# Carranco_shield.net
KiCad netlist of a schematic drawn in EAGLE
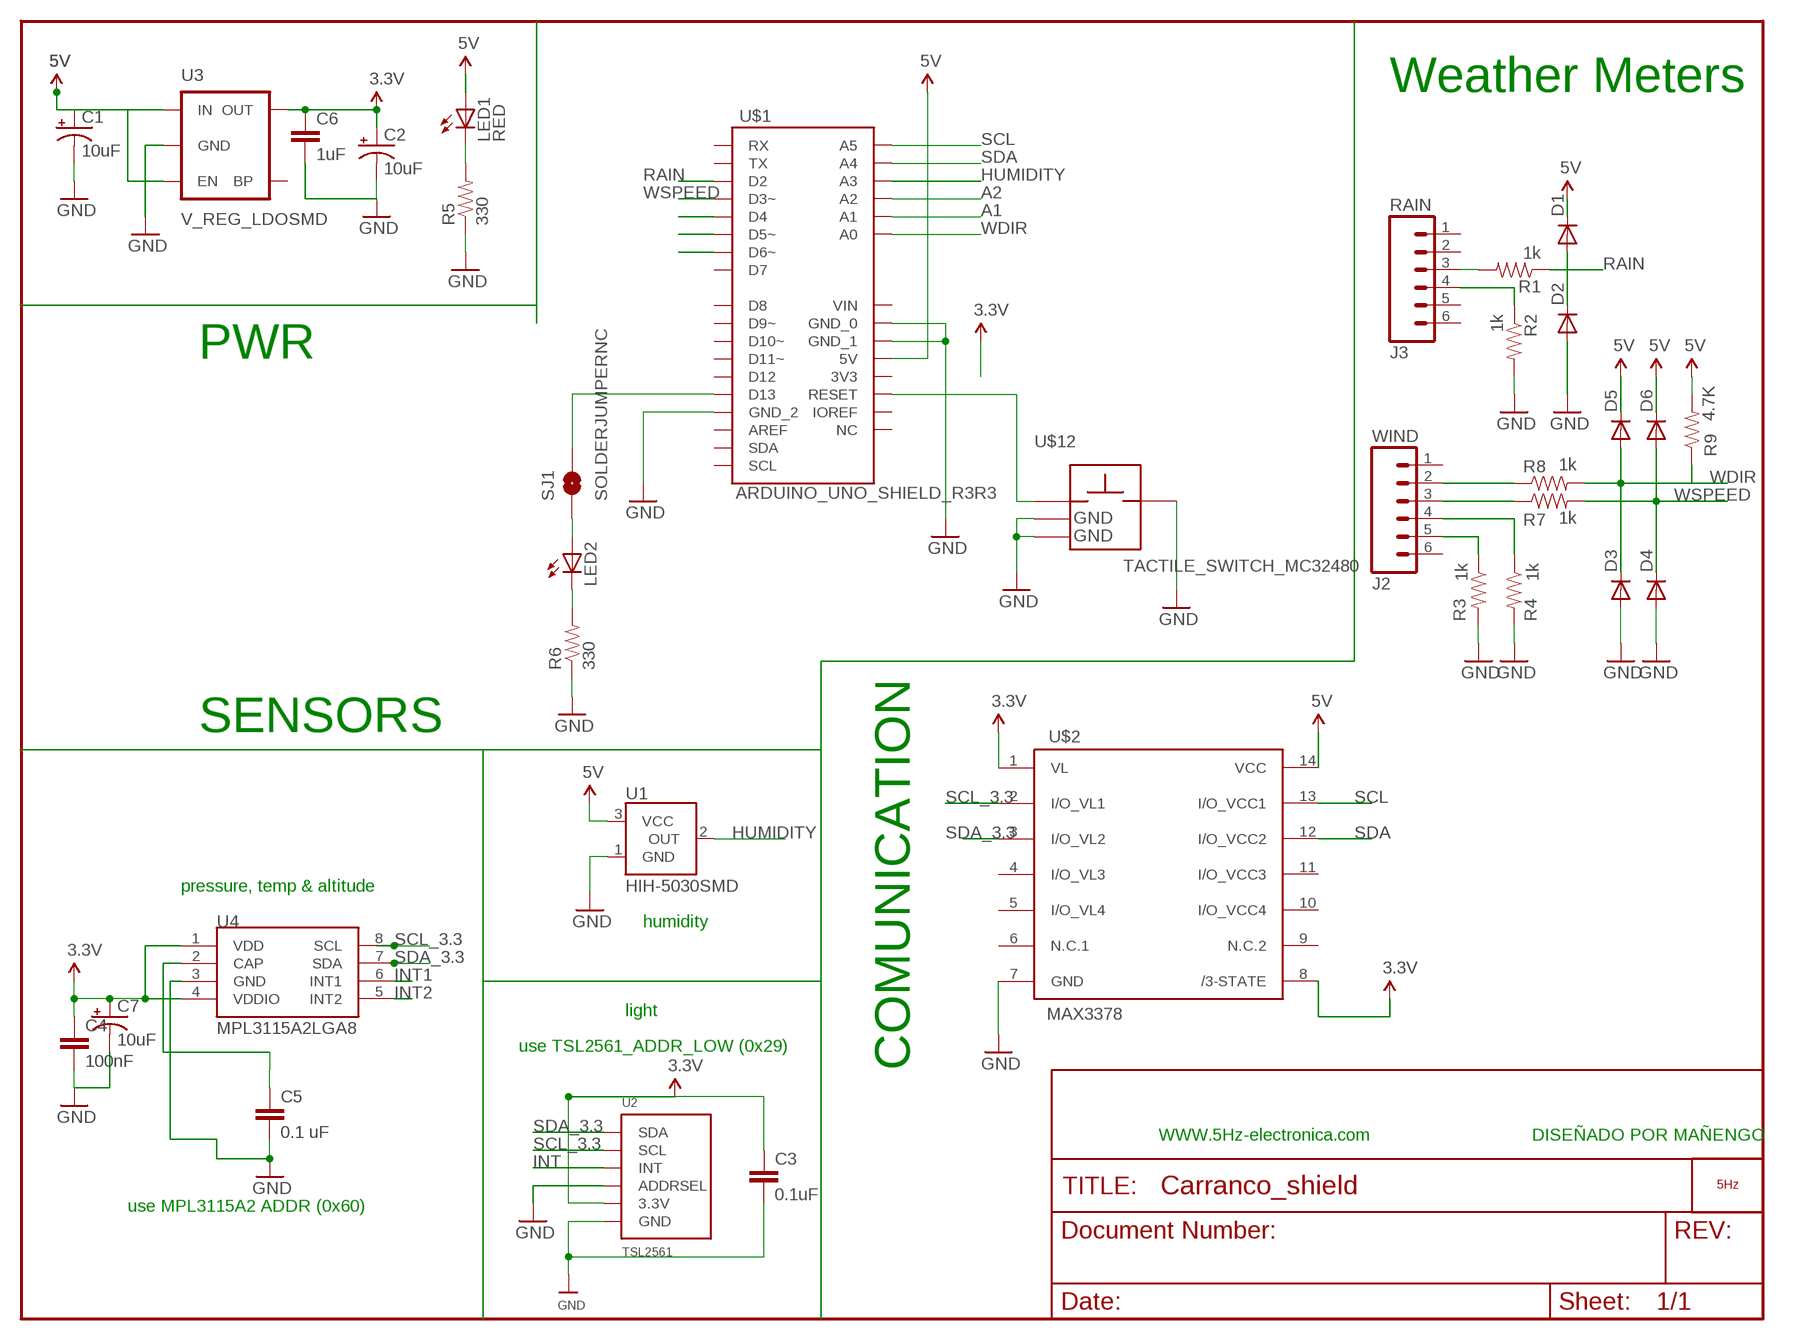
[diagram p0: schematic, sheet 1]

(export (version "E")
  (design (tool "Eeschema 10.0.6"))
  (components
    (comp (ref "C1")
      (value "10uF")
      (footprint "eagle-import:EIA3216")
      (libsource (lib "eagle-import") (part "CAP_POL1206"))
    )
    (comp (ref "C2")
      (value "10uF")
      (footprint "eagle-import:EIA3216")
      (libsource (lib "eagle-import") (part "CAP_POL1206"))
    )
    (comp (ref "C3")
      (value "0.1uF")
      (footprint "eagle-import:0603-CAP")
      (libsource (lib "eagle-import") (part "CAP0603-CAP"))
    )
    (comp (ref "C4")
      (value "100nF")
      (footprint "eagle-import:0603-CAP")
      (libsource (lib "eagle-import") (part "CAP0603-CAP"))
    )
    (comp (ref "C5")
      (value "0.1 uF")
      (footprint "eagle-import:0603-CAP")
      (libsource (lib "eagle-import") (part "CAP0603-CAP"))
    )
    (comp (ref "C6")
      (value "1uF")
      (footprint "eagle-import:0603-CAP")
      (libsource (lib "eagle-import") (part "CAP0603-CAP"))
    )
    (comp (ref "C7")
      (value "10uF")
      (footprint "eagle-import:EIA3216")
      (libsource (lib "eagle-import") (part "CAP_POL1206"))
    )
    (comp (ref "D1")
      (value "DIODESOD")
      (footprint "eagle-import:SOD-323")
      (libsource (lib "eagle-import") (part "DIODESOD"))
    )
    (comp (ref "D2")
      (value "DIODESOD")
      (footprint "eagle-import:SOD-323")
      (libsource (lib "eagle-import") (part "DIODESOD"))
    )
    (comp (ref "D3")
      (value "DIODESOD")
      (footprint "eagle-import:SOD-323")
      (libsource (lib "eagle-import") (part "DIODESOD"))
    )
    (comp (ref "D4")
      (value "DIODESOD")
      (footprint "eagle-import:SOD-323")
      (libsource (lib "eagle-import") (part "DIODESOD"))
    )
    (comp (ref "D5")
      (value "DIODESOD")
      (footprint "eagle-import:SOD-323")
      (libsource (lib "eagle-import") (part "DIODESOD"))
    )
    (comp (ref "D6")
      (value "DIODESOD")
      (footprint "eagle-import:SOD-323")
      (libsource (lib "eagle-import") (part "DIODESOD"))
    )
    (comp (ref "J2")
      (value "WIND")
      (footprint "eagle-import:RJ11-6")
      (libsource (lib "eagle-import") (part "RJ11-6PTH"))
    )
    (comp (ref "J3")
      (value "RAIN")
      (footprint "eagle-import:RJ11-6")
      (libsource (lib "eagle-import") (part "RJ11-6PTH"))
    )
    (comp (ref "LED1")
      (value "RED")
      (footprint "eagle-import:LED-0603")
      (libsource (lib "eagle-import") (part "LED0603"))
    )
    (comp (ref "LED2")
      (value "LED0603")
      (footprint "eagle-import:LED-0603")
      (libsource (lib "eagle-import") (part "LED0603"))
    )
    (comp (ref "LOGO1")
      (value "LOGO_5HZ_H_20MM")
      (footprint "eagle-import:5HZ_LOGO_H_20MM")
      (libsource (lib "eagle-import") (part "LOGO_5HZ_H_20MM"))
    )
    (comp (ref "R1")
      (value "1k")
      (footprint "eagle-import:0603-RES")
      (libsource (lib "eagle-import") (part "RESISTOR0603-RES"))
    )
    (comp (ref "R2")
      (value "1k")
      (footprint "eagle-import:0603-RES")
      (libsource (lib "eagle-import") (part "RESISTOR0603-RES"))
    )
    (comp (ref "R3")
      (value "1k")
      (footprint "eagle-import:0603-RES")
      (libsource (lib "eagle-import") (part "RESISTOR0603-RES"))
    )
    (comp (ref "R4")
      (value "1k")
      (footprint "eagle-import:0603-RES")
      (libsource (lib "eagle-import") (part "RESISTOR0603-RES"))
    )
    (comp (ref "R5")
      (value "330")
      (footprint "eagle-import:0603-RES")
      (libsource (lib "eagle-import") (part "RESISTOR0603-RES"))
    )
    (comp (ref "R6")
      (value "330")
      (footprint "eagle-import:0603-RES")
      (libsource (lib "eagle-import") (part "RESISTOR0603-RES"))
    )
    (comp (ref "R7")
      (value "1k")
      (footprint "eagle-import:0603-RES")
      (libsource (lib "eagle-import") (part "RESISTOR0603-RES"))
    )
    (comp (ref "R8")
      (value "1k")
      (footprint "eagle-import:0603-RES")
      (libsource (lib "eagle-import") (part "RESISTOR0603-RES"))
    )
    (comp (ref "R9")
      (value "4.7K")
      (footprint "eagle-import:0603-RES")
      (libsource (lib "eagle-import") (part "RESISTOR0603-RES"))
    )
    (comp (ref "SJ1")
      (value "SOLDERJUMPERNC")
      (footprint "eagle-import:SJ_2S")
      (libsource (lib "eagle-import") (part "SOLDERJUMPERNC"))
    )
    (comp (ref "U$1")
      (value "ARDUINO_UNO_SHIELD_R3R3")
      (footprint "eagle-import:UNO_R3_SHIELD_HOLES_NO_SILK")
      (libsource (lib "eagle-import") (part "ARDUINO_UNO_SHIELD_R3R3"))
    )
    (comp (ref "U$2")
      (value "MAX3378")
      (footprint "eagle-import:TSSOP14")
      (libsource (lib "eagle-import") (part "MAX3378"))
    )
    (comp (ref "U$12")
      (value "TACTILE_SWITCH_MC32480")
      (footprint "eagle-import:MC32840")
      (libsource (lib "eagle-import") (part "TACTILE_SWITCH_MC32480"))
    )
    (comp (ref "U1")
      (value "HIH-5030SMD")
      (footprint "eagle-import:HIH-5030")
      (libsource (lib "eagle-import") (part "HIH-5030SMD"))
    )
    (comp (ref "U2")
      (value "TSL2561")
      (footprint "eagle-import:TSL2561_FN")
      (libsource (lib "eagle-import") (part "TSL2561"))
    )
    (comp (ref "U3")
      (value "V_REG_LDOSMD")
      (footprint "eagle-import:SOT23-5")
      (libsource (lib "eagle-import") (part "V_REG_LDOSMD"))
    )
    (comp (ref "U4")
      (value "MPL3115A2LGA8")
      (footprint "eagle-import:LGA8")
      (libsource (lib "eagle-import") (part "MPL3115A2LGA8"))
    )
  )
  (nets
    (net (code "1") (name "/A1") (class "Default")
      (node (ref "U$1") (pin "A1") (pinfunction "A1_A1") (pintype "bidirectional"))
    )
    (net (code "2") (name "/A2") (class "Default")
      (node (ref "U$1") (pin "A2") (pinfunction "A2_A2") (pintype "bidirectional"))
    )
    (net (code "3") (name "/HUMIDITY") (class "Default")
      (node (ref "U$1") (pin "A3") (pinfunction "A3_A3") (pintype "bidirectional"))
      (node (ref "U1") (pin "2") (pinfunction "OUT_2") (pintype "bidirectional"))
    )
    (net (code "4") (name "/INT") (class "Default")
      (node (ref "U2") (pin "INT") (pinfunction "INT_INT") (pintype "bidirectional"))
    )
    (net (code "5") (name "/INT1") (class "Default")
      (node (ref "U4") (pin "6") (pinfunction "INT1_6") (pintype "bidirectional"))
    )
    (net (code "6") (name "/INT2") (class "Default")
      (node (ref "U4") (pin "5") (pinfunction "INT2_5") (pintype "bidirectional"))
    )
    (net (code "7") (name "/RAIN") (class "Default")
      (node (ref "D1") (pin "2") (pinfunction "A_2") (pintype "passive"))
      (node (ref "D2") (pin "1") (pinfunction "C_1") (pintype "passive"))
      (node (ref "R1") (pin "1") (pinfunction "1_1") (pintype "passive"))
      (node (ref "U$1") (pin "D2") (pinfunction "D2_D2") (pintype "bidirectional"))
    )
    (net (code "8") (name "/SCL") (class "Default")
      (node (ref "U$1") (pin "A5") (pinfunction "A5_A5") (pintype "bidirectional"))
      (node (ref "U$2") (pin "13") (pinfunction "I/O_VCC1_13") (pintype "bidirectional"))
    )
    (net (code "9") (name "/SCL_3.3") (class "Default")
      (node (ref "U$2") (pin "2") (pinfunction "I/O_VL1_2") (pintype "bidirectional"))
      (node (ref "U2") (pin "CLK") (pinfunction "SCL_CLK") (pintype "bidirectional"))
      (node (ref "U4") (pin "8") (pinfunction "SCL_8") (pintype "bidirectional"))
    )
    (net (code "10") (name "/SDA") (class "Default")
      (node (ref "U$1") (pin "A4") (pinfunction "A4_A4") (pintype "bidirectional"))
      (node (ref "U$2") (pin "12") (pinfunction "I/O_VCC2_12") (pintype "bidirectional"))
    )
    (net (code "11") (name "/SDA_3.3") (class "Default")
      (node (ref "U$2") (pin "3") (pinfunction "I/O_VL2_3") (pintype "bidirectional"))
      (node (ref "U2") (pin "DATA") (pinfunction "SDA_DATA") (pintype "bidirectional"))
      (node (ref "U4") (pin "7") (pinfunction "SDA_7") (pintype "bidirectional"))
    )
    (net (code "12") (name "/WDIR") (class "Default")
      (node (ref "D3") (pin "1") (pinfunction "C_1") (pintype "passive"))
      (node (ref "D5") (pin "2") (pinfunction "A_2") (pintype "passive"))
      (node (ref "R8") (pin "2") (pinfunction "2_2") (pintype "passive"))
      (node (ref "R9") (pin "1") (pinfunction "1_1") (pintype "passive"))
      (node (ref "U$1") (pin "A0") (pinfunction "A0_A0") (pintype "bidirectional"))
    )
    (net (code "13") (name "/WSPEED") (class "Default")
      (node (ref "D4") (pin "1") (pinfunction "C_1") (pintype "passive"))
      (node (ref "D6") (pin "2") (pinfunction "A_2") (pintype "passive"))
      (node (ref "R7") (pin "2") (pinfunction "2_2") (pintype "passive"))
      (node (ref "U$1") (pin "D3") (pinfunction "D3~{}_D3") (pintype "bidirectional"))
    )
    (net (code "14") (name "3.3V") (class "Default")
      (node (ref "C2") (pin "A") (pinfunction "+_A") (pintype "passive"))
      (node (ref "C3") (pin "1") (pinfunction "1_1") (pintype "passive"))
      (node (ref "C4") (pin "1") (pinfunction "1_1") (pintype "passive"))
      (node (ref "C6") (pin "1") (pinfunction "1_1") (pintype "passive"))
      (node (ref "C7") (pin "A") (pinfunction "+_A") (pintype "passive"))
      (node (ref "U$2") (pin "1") (pinfunction "VL_1") (pintype "bidirectional"))
      (node (ref "U$2") (pin "8") (pinfunction "/3-STATE_8") (pintype "bidirectional"))
      (node (ref "U2") (pin "VDD") (pinfunction "3.3V_VDD") (pintype "bidirectional"))
      (node (ref "U3") (pin "5") (pinfunction "OUT_5") (pintype "passive"))
      (node (ref "U4") (pin "1") (pinfunction "VDD_1") (pintype "bidirectional"))
      (node (ref "U4") (pin "4") (pinfunction "VDDIO_4") (pintype "bidirectional"))
    )
    (net (code "15") (name "5V") (class "Default")
      (node (ref "C1") (pin "A") (pinfunction "+_A") (pintype "passive"))
      (node (ref "D1") (pin "1") (pinfunction "C_1") (pintype "passive"))
      (node (ref "D5") (pin "1") (pinfunction "C_1") (pintype "passive"))
      (node (ref "D6") (pin "1") (pinfunction "C_1") (pintype "passive"))
      (node (ref "LED1") (pin "A") (pinfunction "A_A") (pintype "passive"))
      (node (ref "R9") (pin "2") (pinfunction "2_2") (pintype "passive"))
      (node (ref "U$1") (pin "5V") (pinfunction "5V_5V") (pintype "bidirectional"))
      (node (ref "U$2") (pin "14") (pinfunction "VCC_14") (pintype "bidirectional"))
      (node (ref "U1") (pin "3") (pinfunction "VCC_3") (pintype "bidirectional"))
      (node (ref "U3") (pin "1") (pinfunction "IN_1") (pintype "input"))
      (node (ref "U3") (pin "3") (pinfunction "EN_3") (pintype "input"))
    )
    (net (code "16") (name "GND") (class "Default")
      (node (ref "C1") (pin "C") (pinfunction "-_C") (pintype "passive"))
      (node (ref "C2") (pin "C") (pinfunction "-_C") (pintype "passive"))
      (node (ref "C3") (pin "2") (pinfunction "2_2") (pintype "passive"))
      (node (ref "C4") (pin "2") (pinfunction "2_2") (pintype "passive"))
      (node (ref "C5") (pin "2") (pinfunction "2_2") (pintype "passive"))
      (node (ref "C6") (pin "2") (pinfunction "2_2") (pintype "passive"))
      (node (ref "C7") (pin "C") (pinfunction "-_C") (pintype "passive"))
      (node (ref "D2") (pin "2") (pinfunction "A_2") (pintype "passive"))
      (node (ref "D3") (pin "2") (pinfunction "A_2") (pintype "passive"))
      (node (ref "D4") (pin "2") (pinfunction "A_2") (pintype "passive"))
      (node (ref "R2") (pin "2") (pinfunction "2_2") (pintype "passive"))
      (node (ref "R3") (pin "2") (pinfunction "2_2") (pintype "passive"))
      (node (ref "R4") (pin "2") (pinfunction "2_2") (pintype "passive"))
      (node (ref "R5") (pin "1") (pinfunction "1_1") (pintype "passive"))
      (node (ref "R6") (pin "1") (pinfunction "1_1") (pintype "passive"))
      (node (ref "U$1") (pin "GND_0") (pinfunction "GND_0_GND_0") (pintype "bidirectional"))
      (node (ref "U$1") (pin "GND_1") (pinfunction "GND_1_GND_1") (pintype "bidirectional"))
      (node (ref "U$1") (pin "GND_2") (pinfunction "GND_2_GND_2") (pintype "bidirectional"))
      (node (ref "U$12") (pin "B") (pinfunction "B_B") (pintype "passive"))
      (node (ref "U$12") (pin "GND@1") (pinfunction "GND_GND@1") (pintype "bidirectional"))
      (node (ref "U$12") (pin "GND@2") (pinfunction "GND_GND@2") (pintype "bidirectional"))
      (node (ref "U$2") (pin "7") (pinfunction "GND_7") (pintype "bidirectional"))
      (node (ref "U1") (pin "1") (pinfunction "GND_1") (pintype "bidirectional"))
      (node (ref "U2") (pin "ADR") (pinfunction "ADDRSEL_ADR") (pintype "bidirectional"))
      (node (ref "U2") (pin "VSS") (pinfunction "GND_VSS") (pintype "bidirectional"))
      (node (ref "U3") (pin "2") (pinfunction "GND_2") (pintype "input"))
      (node (ref "U4") (pin "3") (pinfunction "GND_3") (pintype "bidirectional"))
    )
    (net (code "17") (name "Net-(J2-Pad2)") (class "Default")
      (node (ref "J2") (pin "2") (pinfunction "2_2") (pintype "passive"))
      (node (ref "R8") (pin "1") (pinfunction "1_1") (pintype "passive"))
    )
    (net (code "18") (name "Net-(J2-Pad3)") (class "Default")
      (node (ref "J2") (pin "3") (pinfunction "3_3") (pintype "passive"))
      (node (ref "R7") (pin "1") (pinfunction "1_1") (pintype "passive"))
    )
    (net (code "19") (name "Net-(J2-Pad4)") (class "Default")
      (node (ref "J2") (pin "4") (pinfunction "4_4") (pintype "passive"))
      (node (ref "R4") (pin "1") (pinfunction "1_1") (pintype "passive"))
    )
    (net (code "20") (name "Net-(J2-Pad5)") (class "Default")
      (node (ref "J2") (pin "5") (pinfunction "5_5") (pintype "passive"))
      (node (ref "R3") (pin "1") (pinfunction "1_1") (pintype "passive"))
    )
    (net (code "21") (name "Net-(J3-Pad3)") (class "Default")
      (node (ref "J3") (pin "3") (pinfunction "3_3") (pintype "passive"))
      (node (ref "R1") (pin "2") (pinfunction "2_2") (pintype "passive"))
    )
    (net (code "22") (name "Net-(J3-Pad4)") (class "Default")
      (node (ref "J3") (pin "4") (pinfunction "4_4") (pintype "passive"))
      (node (ref "R2") (pin "1") (pinfunction "1_1") (pintype "passive"))
    )
    (net (code "23") (name "Net-(LED1-PadC)") (class "Default")
      (node (ref "LED1") (pin "C") (pinfunction "C_C") (pintype "passive"))
      (node (ref "R5") (pin "2") (pinfunction "2_2") (pintype "passive"))
    )
    (net (code "24") (name "Net-(LED2-PadA)") (class "Default")
      (node (ref "LED2") (pin "A") (pinfunction "A_A") (pintype "passive"))
      (node (ref "SJ1") (pin "1") (pinfunction "1_1") (pintype "passive"))
    )
    (net (code "25") (name "Net-(LED2-PadC)") (class "Default")
      (node (ref "LED2") (pin "C") (pinfunction "C_C") (pintype "passive"))
      (node (ref "R6") (pin "2") (pinfunction "2_2") (pintype "passive"))
    )
    (net (code "26") (name "Net-(SJ1-Pad2)") (class "Default")
      (node (ref "SJ1") (pin "2") (pinfunction "2_2") (pintype "passive"))
      (node (ref "U$1") (pin "D13") (pinfunction "D13_D13") (pintype "bidirectional"))
    )
    (net (code "27") (name "Net-(U$1-RESET)") (class "Default")
      (node (ref "U$1") (pin "RES") (pinfunction "RESET_RES") (pintype "bidirectional"))
      (node (ref "U$12") (pin "A@1") (pinfunction "A_A@1") (pintype "passive"))
    )
    (net (code "28") (name "Net-(U4-CAP)") (class "Default")
      (node (ref "C5") (pin "1") (pinfunction "1_1") (pintype "passive"))
      (node (ref "U4") (pin "2") (pinfunction "CAP_2") (pintype "bidirectional"))
    )
    (net (code "29") (name "unconnected-(J2-Pad1)") (class "Default")
      (node (ref "J2") (pin "1") (pinfunction "1_1") (pintype "passive"))
    )
    (net (code "30") (name "unconnected-(J2-Pad6)") (class "Default")
      (node (ref "J2") (pin "6") (pinfunction "6_6") (pintype "passive"))
    )
    (net (code "31") (name "unconnected-(J3-Pad1)") (class "Default")
      (node (ref "J3") (pin "1") (pinfunction "1_1") (pintype "passive"))
    )
    (net (code "32") (name "unconnected-(J3-Pad2)") (class "Default")
      (node (ref "J3") (pin "2") (pinfunction "2_2") (pintype "passive"))
    )
    (net (code "33") (name "unconnected-(J3-Pad5)") (class "Default")
      (node (ref "J3") (pin "5") (pinfunction "5_5") (pintype "passive"))
    )
    (net (code "34") (name "unconnected-(J3-Pad6)") (class "Default")
      (node (ref "J3") (pin "6") (pinfunction "6_6") (pintype "passive"))
    )
    (net (code "35") (name "unconnected-(U$1-3V3-Pad3.3V)") (class "Default")
      (node (ref "U$1") (pin "3.3V") (pinfunction "3V3_3.3V") (pintype "bidirectional"))
    )
    (net (code "36") (name "unconnected-(U$1-D5~{}-PadD5)") (class "Default")
      (node (ref "U$1") (pin "D5") (pinfunction "D5~{}_D5") (pintype "bidirectional"))
    )
    (net (code "37") (name "unconnected-(U$1-D6~{}-PadD6)") (class "Default")
      (node (ref "U$1") (pin "D6") (pinfunction "D6~{}_D6") (pintype "bidirectional"))
    )
    (net (code "38") (name "unconnected-(U$1-D9~{}-PadD9)") (class "Default")
      (node (ref "U$1") (pin "D9") (pinfunction "D9~{}_D9") (pintype "bidirectional"))
    )
    (net (code "39") (name "unconnected-(U$1-D10~{}-PadD10)") (class "Default")
      (node (ref "U$1") (pin "D10") (pinfunction "D10~{}_D10") (pintype "bidirectional"))
    )
    (net (code "40") (name "unconnected-(U$1-D11~{}-PadD11)") (class "Default")
      (node (ref "U$1") (pin "D11") (pinfunction "D11~{}_D11") (pintype "bidirectional"))
    )
    (net (code "41") (name "unconnected-(U$1-PadAREF)") (class "Default")
      (node (ref "U$1") (pin "AREF") (pinfunction "AREF_AREF") (pintype "bidirectional"))
    )
    (net (code "42") (name "unconnected-(U$1-PadD4)") (class "Default")
      (node (ref "U$1") (pin "D4") (pinfunction "D4_D4") (pintype "bidirectional"))
    )
    (net (code "43") (name "unconnected-(U$1-PadD7)") (class "Default")
      (node (ref "U$1") (pin "D7") (pinfunction "D7_D7") (pintype "bidirectional"))
    )
    (net (code "44") (name "unconnected-(U$1-PadD8)") (class "Default")
      (node (ref "U$1") (pin "D8") (pinfunction "D8_D8") (pintype "bidirectional"))
    )
    (net (code "45") (name "unconnected-(U$1-PadD12)") (class "Default")
      (node (ref "U$1") (pin "D12") (pinfunction "D12_D12") (pintype "bidirectional"))
    )
    (net (code "46") (name "unconnected-(U$1-PadIOREF)") (class "Default")
      (node (ref "U$1") (pin "IOREF") (pinfunction "IOREF_IOREF") (pintype "bidirectional"))
    )
    (net (code "47") (name "unconnected-(U$1-PadNC)") (class "Default")
      (node (ref "U$1") (pin "NC") (pinfunction "NC_NC") (pintype "no_connect"))
    )
    (net (code "48") (name "unconnected-(U$1-PadRX)") (class "Default")
      (node (ref "U$1") (pin "RX") (pinfunction "RX_RX") (pintype "bidirectional"))
    )
    (net (code "49") (name "unconnected-(U$1-PadSCL)") (class "Default")
      (node (ref "U$1") (pin "SCL") (pinfunction "SCL_SCL") (pintype "bidirectional"))
    )
    (net (code "50") (name "unconnected-(U$1-PadSDA)") (class "Default")
      (node (ref "U$1") (pin "SDA") (pinfunction "SDA_SDA") (pintype "bidirectional"))
    )
    (net (code "51") (name "unconnected-(U$1-PadTX)") (class "Default")
      (node (ref "U$1") (pin "TX") (pinfunction "TX_TX") (pintype "bidirectional"))
    )
    (net (code "52") (name "unconnected-(U$1-PadVIN)") (class "Default")
      (node (ref "U$1") (pin "VIN") (pinfunction "VIN_VIN") (pintype "bidirectional"))
    )
    (net (code "53") (name "unconnected-(U$2-I{slash}O_VCC3-Pad11)") (class "Default")
      (node (ref "U$2") (pin "11") (pinfunction "I/O_VCC3_11") (pintype "bidirectional"))
    )
    (net (code "54") (name "unconnected-(U$2-I{slash}O_VCC4-Pad10)") (class "Default")
      (node (ref "U$2") (pin "10") (pinfunction "I/O_VCC4_10") (pintype "bidirectional"))
    )
    (net (code "55") (name "unconnected-(U$2-I{slash}O_VL3-Pad4)") (class "Default")
      (node (ref "U$2") (pin "4") (pinfunction "I/O_VL3_4") (pintype "bidirectional"))
    )
    (net (code "56") (name "unconnected-(U$2-I{slash}O_VL4-Pad5)") (class "Default")
      (node (ref "U$2") (pin "5") (pinfunction "I/O_VL4_5") (pintype "bidirectional"))
    )
    (net (code "57") (name "unconnected-(U$2-N.C.1-Pad6)") (class "Default")
      (node (ref "U$2") (pin "6") (pinfunction "N.C.1_6") (pintype "bidirectional"))
    )
    (net (code "58") (name "unconnected-(U$2-N.C.2-Pad9)") (class "Default")
      (node (ref "U$2") (pin "9") (pinfunction "N.C.2_9") (pintype "bidirectional"))
    )
    (net (code "59") (name "unconnected-(U3-BP-Pad4)") (class "Default")
      (node (ref "U3") (pin "4") (pinfunction "BP_4") (pintype "input"))
    )
  )
)
